# LM2596_AMS1117.net
KiCad netlist of a schematic drawn in Altium Designer
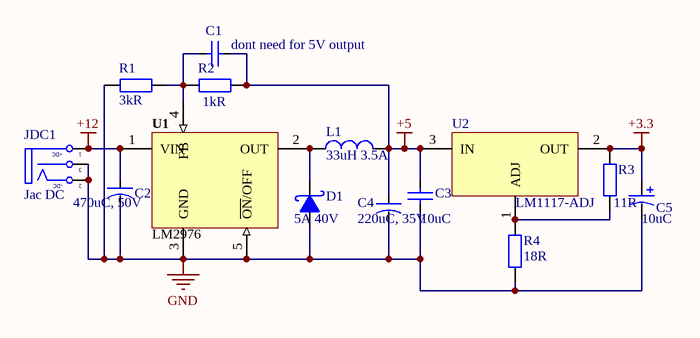
[diagram p0: LM2596 AMS1117.SchDoc]

(export (version "E")
  (design (tool "Eeschema 10.0.6"))
  (components
    (comp (ref "C1")
      (value "dont need for 5V output")
      (footprint "CAP_0402")
      (description "Capacitor")
      (fields (field (name "PUBLISHER") "Altium Limited"))
      (libsource (lib "My Library") (part "CapSMD"))
    )
    (comp (ref "C2")
      (value "470uC, 50V")
      (footprint "CA-ALU-2.54")
      (description "Capacitor (Semiconductor SIM Model)")
      (fields (field (name "PUBLISHER") "Altium Limited"))
      (libsource (lib "My Library") (part "CAP-ALU-DIP"))
    )
    (comp (ref "C3")
      (value "10uC")
      (footprint "CAP_0402")
      (description "Capacitor")
      (fields (field (name "PUBLISHER") "Altium Limited"))
      (libsource (lib "My Library") (part "CapSMD"))
    )
    (comp (ref "C4")
      (value "220uC, 35V")
      (footprint "CA-ALU-2.54")
      (description "Capacitor (Semiconductor SIM Model)")
      (fields (field (name "PUBLISHER") "Altium Limited"))
      (libsource (lib "My Library") (part "CAP-ALU-DIP"))
    )
    (comp (ref "C5")
      (value "10uC")
      (footprint "CAP_7343")
      (description "Polazied Tantalum Capacitor")
      (libsource (lib "My Library") (part "CAP_TAN_SMD"))
    )
    (comp (ref "D1")
      (value "5A 40V")
      (footprint "DIO-3A")
      (description "Generic Diode Schottky")
      (libsource (lib "My Library") (part "Diode Schottky"))
    )
    (comp (ref "JDC1")
      (value "Jac DC")
      (footprint "DC-IN")
      (description "Jac DC input")
      (libsource (lib "My Library") (part "DCIN"))
    )
    (comp (ref "L1")
      (value "33uH 3.5A")
      (footprint "L-SMD-M-12x10")
      (description "Inductor")
      (libsource (lib "My Library") (part "Inductor"))
    )
    (comp (ref "R1")
      (value "3kR")
      (footprint "RES-SMD-0101")
      (description "Resistor SMD")
      (fields
        (field (name "MANUFACTURER") "Generic Components")
        (field (name "PUBLISHER") "Altium Hobart Technology Centre")
      )
      (libsource (lib "My Library") (part "Resistor - SMD"))
    )
    (comp (ref "R2")
      (value "1kR")
      (footprint "RES-SMD-0101")
      (description "Resistor SMD")
      (fields
        (field (name "MANUFACTURER") "Generic Components")
        (field (name "PUBLISHER") "Altium Hobart Technology Centre")
      )
      (libsource (lib "My Library") (part "Resistor - SMD"))
    )
    (comp (ref "R3")
      (value "11R")
      (footprint "RES-SMD-0101")
      (description "Resistor SMD")
      (fields
        (field (name "MANUFACTURER") "Generic Components")
        (field (name "PUBLISHER") "Altium Hobart Technology Centre")
      )
      (libsource (lib "My Library") (part "Resistor - SMD"))
    )
    (comp (ref "R4")
      (value "18R")
      (footprint "RES-SMD-0101")
      (description "Resistor SMD")
      (fields
        (field (name "MANUFACTURER") "Generic Components")
        (field (name "PUBLISHER") "Altium Hobart Technology Centre")
      )
      (libsource (lib "My Library") (part "Resistor - SMD"))
    )
    (comp (ref "U1") (value "LM2976") (footprint "TO-263") (libsource (lib "My Library") (part "LM2596")))
    (comp (ref "U2")
      (value "LM1117-ADJ")
      (footprint "LM1117-SOP")
      (description "800mA Low-Dropout Linear Regulator")
      (fields (field (name "CREATOR") "Nguyen Ba Bien"))
      (libsource (lib "My Library") (part "LM1117-ADJ"))
    )
  )
  (nets
    (net (code "1") (name "+3.3") (class "Default")
      (node (ref "C5") (pin "1") (pinfunction "1_1") (pintype "passive"))
      (node (ref "R3") (pin "1") (pinfunction "1_1") (pintype "passive"))
      (node (ref "U2") (pin "2") (pinfunction "OUT_2") (pintype "passive"))
    )
    (net (code "2") (name "+5") (class "Default")
      (node (ref "C1") (pin "2") (pinfunction "2_2") (pintype "passive"))
      (node (ref "C3") (pin "2") (pinfunction "2_2") (pintype "passive"))
      (node (ref "C4") (pin "1") (pinfunction "1_1") (pintype "passive"))
      (node (ref "L1") (pin "2") (pinfunction "2_2") (pintype "passive"))
      (node (ref "R2") (pin "1") (pinfunction "1_1") (pintype "passive"))
      (node (ref "U2") (pin "3") (pinfunction "IN_3") (pintype "passive"))
    )
    (net (code "3") (name "+12") (class "Default")
      (node (ref "C2") (pin "1") (pinfunction "1_1") (pintype "passive"))
      (node (ref "JDC1") (pin "1") (pinfunction "T_1") (pintype "passive"))
      (node (ref "U1") (pin "1") (pinfunction "VIN_1") (pintype "power_in"))
    )
    (net (code "4") (name "GND") (class "Default")
      (node (ref "C2") (pin "2") (pinfunction "2_2") (pintype "passive"))
      (node (ref "C3") (pin "1") (pinfunction "1_1") (pintype "passive"))
      (node (ref "C4") (pin "2") (pinfunction "2_2") (pintype "passive"))
      (node (ref "C5") (pin "2") (pinfunction "2_2") (pintype "passive"))
      (node (ref "D1") (pin "1") (pinfunction "A_1") (pintype "passive"))
      (node (ref "JDC1") (pin "2") (pinfunction "TN_2") (pintype "passive"))
      (node (ref "JDC1") (pin "3") (pinfunction "S_3") (pintype "power_in"))
      (node (ref "R1") (pin "2") (pinfunction "2_2") (pintype "passive"))
      (node (ref "R4") (pin "2") (pinfunction "2_2") (pintype "passive"))
      (node (ref "U1") (pin "3") (pinfunction "GND_3") (pintype "power_in"))
      (node (ref "U1") (pin "5") (pinfunction "~{ON}/OFF_5") (pintype "input"))
    )
    (net (code "5") (name "Net-(D1-K)") (class "Default")
      (node (ref "D1") (pin "2") (pinfunction "K_2") (pintype "passive"))
      (node (ref "L1") (pin "1") (pinfunction "1_1") (pintype "passive"))
      (node (ref "U1") (pin "2") (pinfunction "OUT_2") (pintype "power_in"))
    )
    (net (code "6") (name "Net-(U1-FB)") (class "Default")
      (node (ref "C1") (pin "1") (pinfunction "1_1") (pintype "passive"))
      (node (ref "R1") (pin "1") (pinfunction "1_1") (pintype "passive"))
      (node (ref "R2") (pin "2") (pinfunction "2_2") (pintype "passive"))
      (node (ref "U1") (pin "4") (pinfunction "FB_4") (pintype "input"))
    )
    (net (code "7") (name "Net-(U2-ADJ)") (class "Default")
      (node (ref "R3") (pin "2") (pinfunction "2_2") (pintype "passive"))
      (node (ref "R4") (pin "1") (pinfunction "1_1") (pintype "passive"))
      (node (ref "U2") (pin "1") (pinfunction "ADJ_1") (pintype "passive"))
    )
  )
)
